# SuperCap_Proto.net
KiCad netlist of a schematic drawn in EAGLE
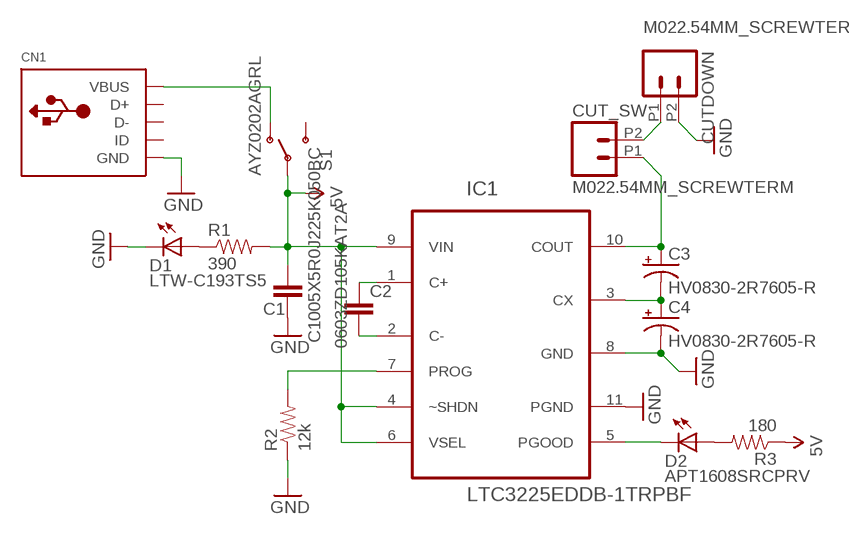
[diagram p0: schematic, sheet 1]

(export (version "E")
  (design (tool "Eeschema 10.0.6"))
  (components
    (comp (ref "C1")
      (value "C1005X5R0J225K050BC")
      (footprint "eagle-import:0402-CAP")
      (libsource (lib "eagle-import") (part "2.2UF-CERCAP-07888"))
    )
    (comp (ref "C2")
      (value "0603ZD105KAT2A")
      (footprint "eagle-import:0603-CAP")
      (libsource (lib "eagle-import") (part "1.0UF-16V-10%(0603)"))
    )
    (comp (ref "C3")
      (value "HV0830-2R7605-R")
      (footprint "eagle-import:CAP_POL_RADIAL_6F_2.7V")
      (libsource (lib "eagle-import") (part "HV0830-2R7605-R"))
    )
    (comp (ref "C4")
      (value "HV0830-2R7605-R")
      (footprint "eagle-import:CAP_POL_RADIAL_6F_2.7V")
      (libsource (lib "eagle-import") (part "HV0830-2R7605-R"))
    )
    (comp (ref "CN1")
      (value "USBMINIB")
      (footprint "eagle-import:USB-MINIB")
      (libsource (lib "eagle-import") (part "USBMINIB"))
    )
    (comp (ref "CUTDOWN")
      (value "M022.54MM_SCREWTERM")
      (footprint "eagle-import:1X02_2.54_SCREWTERM")
      (libsource (lib "eagle-import") (part "M022.54MM_SCREWTERM"))
    )
    (comp (ref "CUT_SW")
      (value "M022.54MM_SCREWTERM")
      (footprint "eagle-import:1X02_2.54_SCREWTERM")
      (libsource (lib "eagle-import") (part "M022.54MM_SCREWTERM"))
    )
    (comp (ref "D1")
      (value "LTW-C193TS5")
      (footprint "eagle-import:LED-0603")
      (libsource (lib "eagle-import") (part "LED0603"))
    )
    (comp (ref "D2")
      (value "APT1608SRCPRV")
      (footprint "eagle-import:LED-0603")
      (libsource (lib "eagle-import") (part "LED-RED0603"))
    )
    (comp (ref "IC1")
      (value "LTC3225EDDB-1TRPBF")
      (footprint "eagle-import:DFN300X200X80")
      (libsource (lib "eagle-import") (part "LTC3225EDDB-1TRPBF"))
    )
    (comp (ref "R1")
      (value "390")
      (footprint "eagle-import:0603-RES")
      (libsource (lib "eagle-import") (part "RESISTOR0603"))
    )
    (comp (ref "R2")
      (value "12k")
      (footprint "eagle-import:0603-RES")
      (libsource (lib "eagle-import") (part "RESISTOR0603"))
    )
    (comp (ref "R3")
      (value "180")
      (footprint "eagle-import:0603-RES")
      (libsource (lib "eagle-import") (part "RESISTOR0603"))
    )
    (comp (ref "S1")
      (value "AYZ0202AGRL")
      (footprint "eagle-import:AYZ0202")
      (libsource (lib "eagle-import") (part "SWITCH-SPDTSMD"))
    )
  )
  (nets
    (net (code "1") (name "5V") (class "Default")
      (node (ref "C1") (pin "1") (pinfunction "1_1") (pintype "passive"))
      (node (ref "IC1") (pin "4") (pinfunction "~{SHDN}_4") (pintype "input"))
      (node (ref "IC1") (pin "6") (pinfunction "VSEL_6") (pintype "input"))
      (node (ref "IC1") (pin "9") (pinfunction "VIN_9") (pintype "power_in"))
      (node (ref "R1") (pin "2") (pinfunction "2_2") (pintype "passive"))
      (node (ref "R3") (pin "1") (pinfunction "1_1") (pintype "passive"))
      (node (ref "S1") (pin "2") (pinfunction "P_2") (pintype "passive"))
    )
    (net (code "2") (name "GND") (class "Default")
      (node (ref "C1") (pin "2") (pinfunction "2_2") (pintype "passive"))
      (node (ref "C4") (pin "P$2") (pinfunction "-_P$2") (pintype "passive"))
      (node (ref "CN1") (pin "GND") (pinfunction "GND_GND") (pintype "power_in"))
      (node (ref "CUTDOWN") (pin "P2") (pinfunction "2_P2") (pintype "passive"))
      (node (ref "D1") (pin "C") (pinfunction "C_C") (pintype "passive"))
      (node (ref "IC1") (pin "11") (pinfunction "PGND_11") (pintype "passive"))
      (node (ref "IC1") (pin "8") (pinfunction "GND_8") (pintype "passive"))
      (node (ref "R2") (pin "1") (pinfunction "1_1") (pintype "passive"))
    )
    (net (code "3") (name "Net-(C3-+)") (class "Default")
      (node (ref "C3") (pin "P$1") (pinfunction "+_P$1") (pintype "passive"))
      (node (ref "CUT_SW") (pin "P1") (pinfunction "1_P1") (pintype "passive"))
      (node (ref "IC1") (pin "10") (pinfunction "COUT_10") (pintype "output"))
    )
    (net (code "4") (name "Net-(C3--)") (class "Default")
      (node (ref "C3") (pin "P$2") (pinfunction "-_P$2") (pintype "passive"))
      (node (ref "C4") (pin "P$1") (pinfunction "+_P$1") (pintype "passive"))
      (node (ref "IC1") (pin "3") (pinfunction "CX_3") (pintype "passive"))
    )
    (net (code "5") (name "Net-(CUTDOWN-1)") (class "Default")
      (node (ref "CUTDOWN") (pin "P1") (pinfunction "1_P1") (pintype "passive"))
      (node (ref "CUT_SW") (pin "P2") (pinfunction "2_P2") (pintype "passive"))
    )
    (net (code "6") (name "Net-(D1-PadA)") (class "Default")
      (node (ref "D1") (pin "A") (pinfunction "A_A") (pintype "passive"))
      (node (ref "R1") (pin "1") (pinfunction "1_1") (pintype "passive"))
    )
    (net (code "7") (name "Net-(D2-PadA)") (class "Default")
      (node (ref "D2") (pin "A") (pinfunction "A_A") (pintype "passive"))
      (node (ref "R3") (pin "2") (pinfunction "2_2") (pintype "passive"))
    )
    (net (code "8") (name "Net-(IC1-C+)") (class "Default")
      (node (ref "C2") (pin "1") (pinfunction "1_1") (pintype "passive"))
      (node (ref "IC1") (pin "1") (pinfunction "C+_1") (pintype "passive"))
    )
    (net (code "9") (name "Net-(IC1-C-)") (class "Default")
      (node (ref "C2") (pin "2") (pinfunction "2_2") (pintype "passive"))
      (node (ref "IC1") (pin "2") (pinfunction "C-_2") (pintype "passive"))
    )
    (net (code "10") (name "Net-(IC1-PGOOD)") (class "Default")
      (node (ref "D2") (pin "C") (pinfunction "C_C") (pintype "passive"))
      (node (ref "IC1") (pin "5") (pinfunction "PGOOD_5") (pintype "output"))
    )
    (net (code "11") (name "Net-(IC1-PROG)") (class "Default")
      (node (ref "IC1") (pin "7") (pinfunction "PROG_7") (pintype "input"))
      (node (ref "R2") (pin "2") (pinfunction "2_2") (pintype "passive"))
    )
    (net (code "12") (name "Net-(S1-O)") (class "Default")
      (node (ref "CN1") (pin "VBUS") (pinfunction "VBUS_VBUS") (pintype "power_in"))
      (node (ref "S1") (pin "1") (pinfunction "O_1") (pintype "passive"))
    )
    (net (code "13") (name "unconnected-(CN1-PadD+)") (class "Default")
      (node (ref "CN1") (pin "D+") (pinfunction "D+_D+") (pintype "bidirectional"))
    )
    (net (code "14") (name "unconnected-(CN1-PadD-)") (class "Default")
      (node (ref "CN1") (pin "D-") (pinfunction "D-_D-") (pintype "bidirectional"))
    )
    (net (code "15") (name "unconnected-(CN1-PadID)") (class "Default")
      (node (ref "CN1") (pin "ID") (pinfunction "ID_ID") (pintype "bidirectional"))
    )
    (net (code "16") (name "unconnected-(S1-S-Pad3)") (class "Default")
      (node (ref "S1") (pin "3") (pinfunction "S_3") (pintype "passive"))
    )
  )
)
